# WSN_Gateway_v4_2.net
KiCad netlist of a schematic drawn in EAGLE
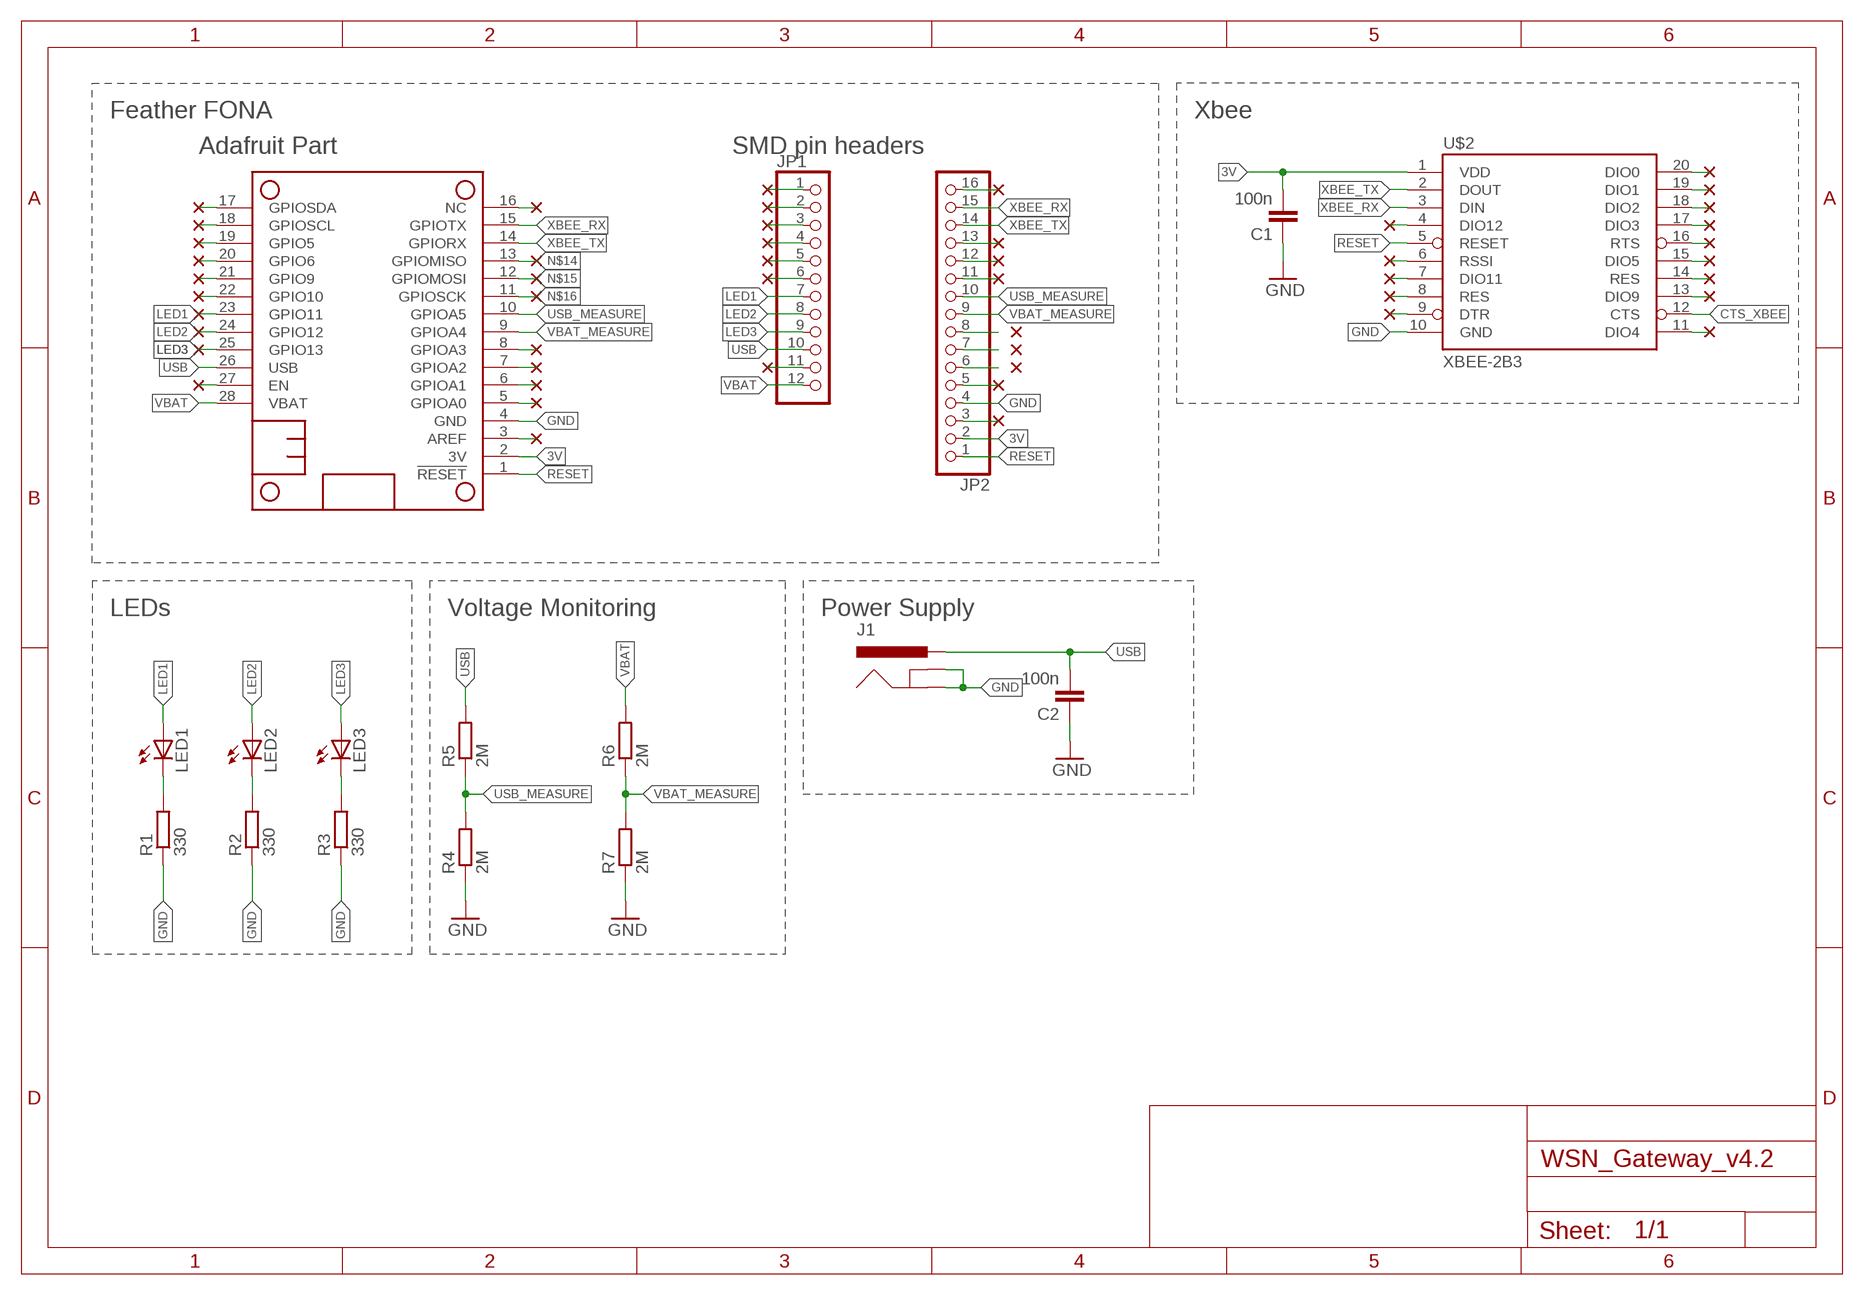
[diagram p0: schematic, sheet 1]

(export (version "E")
  (design (tool "Eeschema 10.0.6"))
  (components
    (comp (ref "C1")
      (value "100n")
      (footprint "eagle-import:C0805")
      (libsource (lib "eagle-import") (part "C"))
    )
    (comp (ref "C2")
      (value "100n")
      (footprint "eagle-import:C0805")
      (libsource (lib "eagle-import") (part "C"))
    )
    (comp (ref "J1")
      (value "5.5x2.1mm Barrel")
      (footprint "eagle-import:POWER_JACK_SMD")
      (libsource (lib "eagle-import") (part "POWER_JACKSMD"))
    )
    (comp (ref "JP1")
      (value "PINHD-1X121X12_SMT")
      (footprint "eagle-import:1X12_SMT")
      (libsource (lib "eagle-import") (part "PINHD-1X121X12_SMT"))
    )
    (comp (ref "JP2")
      (value "PINHD-1X161X16_SMT")
      (footprint "eagle-import:1X16_SMT")
      (libsource (lib "eagle-import") (part "PINHD-1X161X16_SMT"))
    )
    (comp (ref "LED1")
      (value "LEDCHIPLED_0805")
      (footprint "eagle-import:CHIPLED_0805")
      (libsource (lib "eagle-import") (part "LEDCHIPLED_0805"))
    )
    (comp (ref "LED2")
      (value "LEDCHIPLED_0805")
      (footprint "eagle-import:CHIPLED_0805")
      (libsource (lib "eagle-import") (part "LEDCHIPLED_0805"))
    )
    (comp (ref "LED3")
      (value "LEDCHIPLED_0805")
      (footprint "eagle-import:CHIPLED_0805")
      (libsource (lib "eagle-import") (part "LEDCHIPLED_0805"))
    )
    (comp (ref "MS1")
      (value "FEATHERWING_NODIM_NOHOLES")
      (footprint "eagle-import:FEATHERWING_DIM_2")
      (libsource (lib "eagle-import") (part "FEATHERWING_NODIM_NOHOLES"))
    )
    (comp (ref "R1")
      (value "330")
      (footprint "eagle-import:R0805")
      (libsource (lib "eagle-import") (part "R-EU_R0805"))
    )
    (comp (ref "R2")
      (value "330")
      (footprint "eagle-import:R0805")
      (libsource (lib "eagle-import") (part "R-EU_R0805"))
    )
    (comp (ref "R3")
      (value "330")
      (footprint "eagle-import:R0805")
      (libsource (lib "eagle-import") (part "R-EU_R0805"))
    )
    (comp (ref "R4")
      (value "2M")
      (footprint "eagle-import:R0805")
      (libsource (lib "eagle-import") (part "R-EU_R0805"))
    )
    (comp (ref "R5")
      (value "2M")
      (footprint "eagle-import:R0805")
      (libsource (lib "eagle-import") (part "R-EU_R0805"))
    )
    (comp (ref "R6")
      (value "2M")
      (footprint "eagle-import:R0805")
      (libsource (lib "eagle-import") (part "R-EU_R0805"))
    )
    (comp (ref "R7")
      (value "2M")
      (footprint "eagle-import:R0805")
      (libsource (lib "eagle-import") (part "R-EU_R0805"))
    )
    (comp (ref "U$2")
      (value "XBEE-2B3")
      (footprint "eagle-import:XBEE-SMD")
      (libsource (lib "eagle-import") (part "XBEE-2B3"))
    )
  )
  (nets
    (net (code "1") (name "/NC6") (class "Default")
      (node (ref "JP2") (pin "6") (pinfunction "6_6") (pintype "passive"))
      (node (ref "MS1") (pin "6") (pinfunction "GPIOA1_6") (pintype "bidirectional"))
    )
    (net (code "2") (name "/NC7") (class "Default")
      (node (ref "JP2") (pin "7") (pinfunction "7_7") (pintype "passive"))
      (node (ref "MS1") (pin "7") (pinfunction "GPIOA2_7") (pintype "bidirectional"))
    )
    (net (code "3") (name "/NC8") (class "Default")
      (node (ref "JP2") (pin "8") (pinfunction "8_8") (pintype "passive"))
      (node (ref "MS1") (pin "8") (pinfunction "GPIOA3_8") (pintype "bidirectional"))
    )
    (net (code "4") (name "3V") (class "Default")
      (node (ref "C1") (pin "2") (pinfunction "2_2") (pintype "passive"))
      (node (ref "JP2") (pin "2") (pinfunction "2_2") (pintype "passive"))
      (node (ref "MS1") (pin "2") (pinfunction "3V_2") (pintype "power_in"))
      (node (ref "U$2") (pin "1") (pinfunction "VDD_1") (pintype "power_in"))
    )
    (net (code "5") (name "CTS_XBEE") (class "Default")
      (node (ref "U$2") (pin "12") (pinfunction "CTS_12") (pintype "output"))
    )
    (net (code "6") (name "GND") (class "Default")
      (node (ref "C1") (pin "1") (pinfunction "1_1") (pintype "passive"))
      (node (ref "C2") (pin "1") (pinfunction "1_1") (pintype "passive"))
      (node (ref "J1") (pin "GND") (pinfunction "GNDBREAK_GND") (pintype "bidirectional"))
      (node (ref "J1") (pin "P$4") (pinfunction "GND_P$4") (pintype "bidirectional"))
      (node (ref "JP2") (pin "4") (pinfunction "4_4") (pintype "passive"))
      (node (ref "MS1") (pin "4") (pinfunction "GND_4") (pintype "power_in"))
      (node (ref "R1") (pin "1") (pinfunction "1_1") (pintype "passive"))
      (node (ref "R2") (pin "1") (pinfunction "1_1") (pintype "passive"))
      (node (ref "R3") (pin "1") (pinfunction "1_1") (pintype "passive"))
      (node (ref "R4") (pin "1") (pinfunction "1_1") (pintype "passive"))
      (node (ref "R7") (pin "1") (pinfunction "1_1") (pintype "passive"))
      (node (ref "U$2") (pin "10") (pinfunction "GND_10") (pintype "power_in"))
    )
    (net (code "7") (name "LED1") (class "Default")
      (node (ref "JP1") (pin "7") (pinfunction "7_7") (pintype "passive"))
      (node (ref "LED1") (pin "A") (pinfunction "A_A") (pintype "passive"))
      (node (ref "MS1") (pin "23") (pinfunction "GPIO11_23") (pintype "bidirectional"))
    )
    (net (code "8") (name "LED2") (class "Default")
      (node (ref "JP1") (pin "8") (pinfunction "8_8") (pintype "passive"))
      (node (ref "LED2") (pin "A") (pinfunction "A_A") (pintype "passive"))
      (node (ref "MS1") (pin "24") (pinfunction "GPIO12_24") (pintype "bidirectional"))
    )
    (net (code "9") (name "LED3") (class "Default")
      (node (ref "JP1") (pin "9") (pinfunction "9_9") (pintype "passive"))
      (node (ref "LED3") (pin "A") (pinfunction "A_A") (pintype "passive"))
      (node (ref "MS1") (pin "25") (pinfunction "GPIO13_25") (pintype "bidirectional"))
    )
    (net (code "10") (name "N$14") (class "Default")
      (node (ref "MS1") (pin "13") (pinfunction "GPIOMISO_13") (pintype "bidirectional"))
    )
    (net (code "11") (name "N$15") (class "Default")
      (node (ref "MS1") (pin "12") (pinfunction "GPIOMOSI_12") (pintype "bidirectional"))
    )
    (net (code "12") (name "N$16") (class "Default")
      (node (ref "MS1") (pin "11") (pinfunction "GPIOSCK_11") (pintype "bidirectional"))
    )
    (net (code "13") (name "Net-(LED1-PadC)") (class "Default")
      (node (ref "LED1") (pin "C") (pinfunction "C_C") (pintype "passive"))
      (node (ref "R1") (pin "2") (pinfunction "2_2") (pintype "passive"))
    )
    (net (code "14") (name "Net-(LED2-PadC)") (class "Default")
      (node (ref "LED2") (pin "C") (pinfunction "C_C") (pintype "passive"))
      (node (ref "R2") (pin "2") (pinfunction "2_2") (pintype "passive"))
    )
    (net (code "15") (name "Net-(LED3-PadC)") (class "Default")
      (node (ref "LED3") (pin "C") (pinfunction "C_C") (pintype "passive"))
      (node (ref "R3") (pin "2") (pinfunction "2_2") (pintype "passive"))
    )
    (net (code "16") (name "RESET") (class "Default")
      (node (ref "JP2") (pin "1") (pinfunction "1_1") (pintype "passive"))
      (node (ref "MS1") (pin "1") (pinfunction "~{RESET}_1") (pintype "input"))
      (node (ref "U$2") (pin "5") (pinfunction "RESET_5") (pintype "input"))
    )
    (net (code "17") (name "USB") (class "Default")
      (node (ref "C2") (pin "2") (pinfunction "2_2") (pintype "passive"))
      (node (ref "J1") (pin "VIN0") (pinfunction "PWR_VIN0") (pintype "bidirectional"))
      (node (ref "J1") (pin "VIN1") (pinfunction "PWR_VIN1") (pintype "bidirectional"))
      (node (ref "JP1") (pin "10") (pinfunction "10_10") (pintype "passive"))
      (node (ref "MS1") (pin "26") (pinfunction "USB_26") (pintype "power_in"))
      (node (ref "R5") (pin "2") (pinfunction "2_2") (pintype "passive"))
    )
    (net (code "18") (name "USB_MEASURE") (class "Default")
      (node (ref "JP2") (pin "10") (pinfunction "10_10") (pintype "passive"))
      (node (ref "MS1") (pin "10") (pinfunction "GPIOA5_10") (pintype "bidirectional"))
      (node (ref "R4") (pin "2") (pinfunction "2_2") (pintype "passive"))
      (node (ref "R5") (pin "1") (pinfunction "1_1") (pintype "passive"))
    )
    (net (code "19") (name "VBAT") (class "Default")
      (node (ref "JP1") (pin "12") (pinfunction "12_12") (pintype "passive"))
      (node (ref "MS1") (pin "28") (pinfunction "VBAT_28") (pintype "power_in"))
      (node (ref "R6") (pin "2") (pinfunction "2_2") (pintype "passive"))
    )
    (net (code "20") (name "VBAT_MEASURE") (class "Default")
      (node (ref "JP2") (pin "9") (pinfunction "9_9") (pintype "passive"))
      (node (ref "MS1") (pin "9") (pinfunction "GPIOA4_9") (pintype "bidirectional"))
      (node (ref "R6") (pin "1") (pinfunction "1_1") (pintype "passive"))
      (node (ref "R7") (pin "2") (pinfunction "2_2") (pintype "passive"))
    )
    (net (code "21") (name "XBEE_RX") (class "Default")
      (node (ref "JP2") (pin "15") (pinfunction "15_15") (pintype "passive"))
      (node (ref "MS1") (pin "15") (pinfunction "GPIOTX_15") (pintype "bidirectional"))
      (node (ref "U$2") (pin "3") (pinfunction "DIN_3") (pintype "input"))
    )
    (net (code "22") (name "XBEE_TX") (class "Default")
      (node (ref "JP2") (pin "14") (pinfunction "14_14") (pintype "passive"))
      (node (ref "MS1") (pin "14") (pinfunction "GPIORX_14") (pintype "bidirectional"))
      (node (ref "U$2") (pin "2") (pinfunction "DOUT_2") (pintype "output"))
    )
    (net (code "23") (name "unconnected-(JP1-Pad1)") (class "Default")
      (node (ref "JP1") (pin "1") (pinfunction "1_1") (pintype "passive"))
    )
    (net (code "24") (name "unconnected-(JP1-Pad2)") (class "Default")
      (node (ref "JP1") (pin "2") (pinfunction "2_2") (pintype "passive"))
    )
    (net (code "25") (name "unconnected-(JP1-Pad3)") (class "Default")
      (node (ref "JP1") (pin "3") (pinfunction "3_3") (pintype "passive"))
    )
    (net (code "26") (name "unconnected-(JP1-Pad4)") (class "Default")
      (node (ref "JP1") (pin "4") (pinfunction "4_4") (pintype "passive"))
    )
    (net (code "27") (name "unconnected-(JP1-Pad5)") (class "Default")
      (node (ref "JP1") (pin "5") (pinfunction "5_5") (pintype "passive"))
    )
    (net (code "28") (name "unconnected-(JP1-Pad6)") (class "Default")
      (node (ref "JP1") (pin "6") (pinfunction "6_6") (pintype "passive"))
    )
    (net (code "29") (name "unconnected-(JP1-Pad11)") (class "Default")
      (node (ref "JP1") (pin "11") (pinfunction "11_11") (pintype "passive"))
    )
    (net (code "30") (name "unconnected-(JP2-Pad3)") (class "Default")
      (node (ref "JP2") (pin "3") (pinfunction "3_3") (pintype "passive"))
    )
    (net (code "31") (name "unconnected-(JP2-Pad5)") (class "Default")
      (node (ref "JP2") (pin "5") (pinfunction "5_5") (pintype "passive"))
    )
    (net (code "32") (name "unconnected-(JP2-Pad11)") (class "Default")
      (node (ref "JP2") (pin "11") (pinfunction "11_11") (pintype "passive"))
    )
    (net (code "33") (name "unconnected-(JP2-Pad12)") (class "Default")
      (node (ref "JP2") (pin "12") (pinfunction "12_12") (pintype "passive"))
    )
    (net (code "34") (name "unconnected-(JP2-Pad13)") (class "Default")
      (node (ref "JP2") (pin "13") (pinfunction "13_13") (pintype "passive"))
    )
    (net (code "35") (name "unconnected-(JP2-Pad16)") (class "Default")
      (node (ref "JP2") (pin "16") (pinfunction "16_16") (pintype "passive"))
    )
    (net (code "36") (name "unconnected-(MS1-AREF-Pad3)") (class "Default")
      (node (ref "MS1") (pin "3") (pinfunction "AREF_3") (pintype "passive"))
    )
    (net (code "37") (name "unconnected-(MS1-EN-Pad27)") (class "Default")
      (node (ref "MS1") (pin "27") (pinfunction "EN_27") (pintype "passive"))
    )
    (net (code "38") (name "unconnected-(MS1-GPIO5-Pad19)") (class "Default")
      (node (ref "MS1") (pin "19") (pinfunction "GPIO5_19") (pintype "bidirectional"))
    )
    (net (code "39") (name "unconnected-(MS1-GPIO6-Pad20)") (class "Default")
      (node (ref "MS1") (pin "20") (pinfunction "GPIO6_20") (pintype "bidirectional"))
    )
    (net (code "40") (name "unconnected-(MS1-GPIO9-Pad21)") (class "Default")
      (node (ref "MS1") (pin "21") (pinfunction "GPIO9_21") (pintype "bidirectional"))
    )
    (net (code "41") (name "unconnected-(MS1-GPIO10-Pad22)") (class "Default")
      (node (ref "MS1") (pin "22") (pinfunction "GPIO10_22") (pintype "bidirectional"))
    )
    (net (code "42") (name "unconnected-(MS1-GPIOA0-Pad5)") (class "Default")
      (node (ref "MS1") (pin "5") (pinfunction "GPIOA0_5") (pintype "bidirectional"))
    )
    (net (code "43") (name "unconnected-(MS1-GPIOSCL-Pad18)") (class "Default")
      (node (ref "MS1") (pin "18") (pinfunction "GPIOSCL_18") (pintype "bidirectional"))
    )
    (net (code "44") (name "unconnected-(MS1-GPIOSDA-Pad17)") (class "Default")
      (node (ref "MS1") (pin "17") (pinfunction "GPIOSDA_17") (pintype "bidirectional"))
    )
    (net (code "45") (name "unconnected-(MS1-NC-Pad16)") (class "Default")
      (node (ref "MS1") (pin "16") (pinfunction "NC_16") (pintype "passive"))
    )
    (net (code "46") (name "unconnected-(U$2-DIO0-Pad20)") (class "Default")
      (node (ref "U$2") (pin "20") (pinfunction "DIO0_20") (pintype "bidirectional"))
    )
    (net (code "47") (name "unconnected-(U$2-DIO1-Pad19)") (class "Default")
      (node (ref "U$2") (pin "19") (pinfunction "DIO1_19") (pintype "bidirectional"))
    )
    (net (code "48") (name "unconnected-(U$2-DIO2-Pad18)") (class "Default")
      (node (ref "U$2") (pin "18") (pinfunction "DIO2_18") (pintype "bidirectional"))
    )
    (net (code "49") (name "unconnected-(U$2-DIO3-Pad17)") (class "Default")
      (node (ref "U$2") (pin "17") (pinfunction "DIO3_17") (pintype "bidirectional"))
    )
    (net (code "50") (name "unconnected-(U$2-DIO4-Pad11)") (class "Default")
      (node (ref "U$2") (pin "11") (pinfunction "DIO4_11") (pintype "bidirectional"))
    )
    (net (code "51") (name "unconnected-(U$2-DIO5-Pad15)") (class "Default")
      (node (ref "U$2") (pin "15") (pinfunction "DIO5_15") (pintype "bidirectional"))
    )
    (net (code "52") (name "unconnected-(U$2-DIO9-Pad13)") (class "Default")
      (node (ref "U$2") (pin "13") (pinfunction "DIO9_13") (pintype "bidirectional"))
    )
    (net (code "53") (name "unconnected-(U$2-DIO11-Pad7)") (class "Default")
      (node (ref "U$2") (pin "7") (pinfunction "DIO11_7") (pintype "bidirectional"))
    )
    (net (code "54") (name "unconnected-(U$2-DIO12-Pad4)") (class "Default")
      (node (ref "U$2") (pin "4") (pinfunction "DIO12_4") (pintype "bidirectional"))
    )
    (net (code "55") (name "unconnected-(U$2-DTR-Pad9)") (class "Default")
      (node (ref "U$2") (pin "9") (pinfunction "DTR_9") (pintype "bidirectional"))
    )
    (net (code "56") (name "unconnected-(U$2-RES-Pad8)") (class "Default")
      (node (ref "U$2") (pin "8") (pinfunction "RES_8") (pintype "bidirectional"))
    )
    (net (code "57") (name "unconnected-(U$2-RES-Pad14)") (class "Default")
      (node (ref "U$2") (pin "14") (pinfunction "RES_14") (pintype "bidirectional"))
    )
    (net (code "58") (name "unconnected-(U$2-RSSI-Pad6)") (class "Default")
      (node (ref "U$2") (pin "6") (pinfunction "RSSI_6") (pintype "bidirectional"))
    )
    (net (code "59") (name "unconnected-(U$2-RTS-Pad16)") (class "Default")
      (node (ref "U$2") (pin "16") (pinfunction "RTS_16") (pintype "input"))
    )
  )
)
